# ACESJouleThief0PCMnt.net
KiCad netlist of a schematic drawn in EAGLE
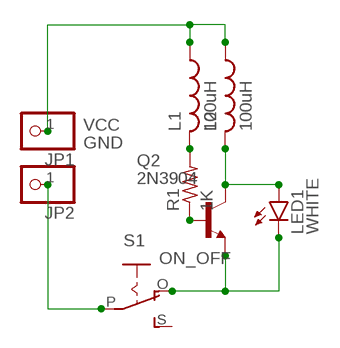
[diagram p0: schematic, sheet 1]

(export (version "E")
  (design (tool "Eeschema 10.0.6"))
  (components
    (comp (ref "JP1")
      (value "PINHD-1X1")
      (footprint "eagle-import:1X01")
      (libsource (lib "eagle-import") (part "PINHD-1X1"))
    )
    (comp (ref "JP2")
      (value "PINHD-1X1")
      (footprint "eagle-import:1X01")
      (libsource (lib "eagle-import") (part "PINHD-1X1"))
    )
    (comp (ref "L1")
      (value "100uH")
      (footprint "eagle-import:0207_10")
      (libsource (lib "eagle-import") (part "L-US0207/10"))
    )
    (comp (ref "L2")
      (value "100uH")
      (footprint "eagle-import:0207_10")
      (libsource (lib "eagle-import") (part "L-US0207/10"))
    )
    (comp (ref "LED1")
      (value "WHITE")
      (footprint "eagle-import:LED_5MM")
      (libsource (lib "eagle-import") (part "LED5MM"))
    )
    (comp (ref "Q2")
      (value "2N3904")
      (footprint "eagle-import:TO92-EBC")
      (libsource (lib "eagle-import") (part "-NPN-TO92-EBC29"))
    )
    (comp (ref "R1")
      (value "1K")
      (footprint "eagle-import:0207_10")
      (libsource (lib "eagle-import") (part "R-US_0207/10"))
    )
    (comp (ref "S1")
      (value "ON_OFF")
      (footprint "eagle-import:EG1218")
      (libsource (lib "eagle-import") (part "EG1218S"))
    )
  )
  (nets
    (net (code "1") (name "/GND") (class "Default")
      (node (ref "JP2") (pin "1") (pinfunction "1_1") (pintype "passive"))
      (node (ref "S1") (pin "P") (pinfunction "P_P") (pintype "passive"))
    )
    (net (code "2") (name "/VCC") (class "Default")
      (node (ref "JP1") (pin "1") (pinfunction "1_1") (pintype "passive"))
      (node (ref "L1") (pin "1") (pinfunction "1_1") (pintype "passive"))
      (node (ref "L2") (pin "1") (pinfunction "1_1") (pintype "passive"))
    )
    (net (code "3") (name "Net-(L1-Pad2)") (class "Default")
      (node (ref "L1") (pin "2") (pinfunction "2_2") (pintype "passive"))
      (node (ref "R1") (pin "2") (pinfunction "2_2") (pintype "passive"))
    )
    (net (code "4") (name "Net-(L2-Pad2)") (class "Default")
      (node (ref "L2") (pin "2") (pinfunction "2_2") (pintype "passive"))
      (node (ref "LED1") (pin "A") (pinfunction "A_A") (pintype "passive"))
      (node (ref "Q2") (pin "C") (pinfunction "C_C") (pintype "passive"))
    )
    (net (code "5") (name "Net-(LED1-C)") (class "Default")
      (node (ref "LED1") (pin "K") (pinfunction "C_K") (pintype "passive"))
      (node (ref "Q2") (pin "E") (pinfunction "E_E") (pintype "passive"))
      (node (ref "S1") (pin "O") (pinfunction "O_O") (pintype "passive"))
    )
    (net (code "6") (name "Net-(Q2-PadB)") (class "Default")
      (node (ref "Q2") (pin "B") (pinfunction "B_B") (pintype "passive"))
      (node (ref "R1") (pin "1") (pinfunction "1_1") (pintype "passive"))
    )
    (net (code "7") (name "unconnected-(S1-PadS)") (class "Default")
      (node (ref "S1") (pin "S") (pinfunction "S_S") (pintype "passive"))
    )
  )
)
